# Placa_1.net
KiCad netlist of a schematic drawn in EAGLE
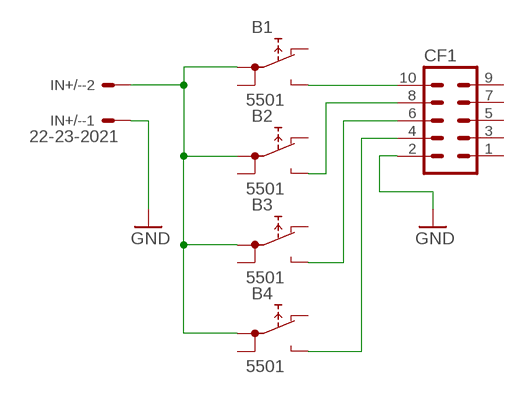
[diagram p0: schematic, sheet 1]

(export (version "E")
  (design (tool "Eeschema 10.0.6"))
  (components
    (comp (ref "B1")
      (value "5501")
      (footprint "eagle-import:5501")
      (libsource (lib "eagle-import") (part "55?01"))
    )
    (comp (ref "B2")
      (value "5501")
      (footprint "eagle-import:5501")
      (libsource (lib "eagle-import") (part "55?01"))
    )
    (comp (ref "B3")
      (value "5501")
      (footprint "eagle-import:5501")
      (libsource (lib "eagle-import") (part "55?01"))
    )
    (comp (ref "B4")
      (value "5501")
      (footprint "eagle-import:5501")
      (libsource (lib "eagle-import") (part "55?01"))
    )
    (comp (ref "CF1")
      (value "ML10")
      (footprint "eagle-import:ML10")
      (libsource (lib "eagle-import") (part "ML10"))
    )
    (comp (ref "IN+/-")
      (value "22-23-2021")
      (footprint "eagle-import:22-23-2021")
      (fields (field (name "MF") "MOLEX"))
      (libsource (lib "eagle-import") (part "22-23-2021"))
    )
  )
  (nets
    (net (code "1") (name "GND") (class "Default")
      (node (ref "CF1") (pin "2") (pinfunction "2_2") (pintype "passive"))
      (node (ref "IN+/-") (pin "1") (pinfunction "S_1") (pintype "passive"))
    )
    (net (code "2") (name "Net-(B1-PadNO)") (class "Default")
      (node (ref "B1") (pin "NO") (pinfunction "NO_NO") (pintype "passive"))
      (node (ref "CF1") (pin "10") (pinfunction "10_10") (pintype "passive"))
    )
    (net (code "3") (name "Net-(B2-PadNO)") (class "Default")
      (node (ref "B2") (pin "NO") (pinfunction "NO_NO") (pintype "passive"))
      (node (ref "CF1") (pin "8") (pinfunction "8_8") (pintype "passive"))
    )
    (net (code "4") (name "Net-(B3-PadNO)") (class "Default")
      (node (ref "B3") (pin "NO") (pinfunction "NO_NO") (pintype "passive"))
      (node (ref "CF1") (pin "6") (pinfunction "6_6") (pintype "passive"))
    )
    (net (code "5") (name "Net-(B4-PadNO)") (class "Default")
      (node (ref "B4") (pin "NO") (pinfunction "NO_NO") (pintype "passive"))
      (node (ref "CF1") (pin "4") (pinfunction "4_4") (pintype "passive"))
    )
    (net (code "6") (name "Net-(IN+/-B-S)") (class "Default")
      (node (ref "B1") (pin "1A") (pinfunction "1A_1A") (pintype "passive"))
      (node (ref "B2") (pin "1A") (pinfunction "1A_1A") (pintype "passive"))
      (node (ref "B3") (pin "1A") (pinfunction "1A_1A") (pintype "passive"))
      (node (ref "B4") (pin "1A") (pinfunction "1A_1A") (pintype "passive"))
      (node (ref "IN+/-") (pin "2") (pinfunction "S_2") (pintype "passive"))
    )
    (net (code "7") (name "unconnected-(B1-Pad1B)") (class "Default")
      (node (ref "B1") (pin "1B") (pinfunction "1B_1B") (pintype "passive"))
    )
    (net (code "8") (name "unconnected-(B1-PadNC)") (class "Default")
      (node (ref "B1") (pin "NC") (pinfunction "NC_NC") (pintype "passive"))
    )
    (net (code "9") (name "unconnected-(B2-Pad1B)") (class "Default")
      (node (ref "B2") (pin "1B") (pinfunction "1B_1B") (pintype "passive"))
    )
    (net (code "10") (name "unconnected-(B2-PadNC)") (class "Default")
      (node (ref "B2") (pin "NC") (pinfunction "NC_NC") (pintype "passive"))
    )
    (net (code "11") (name "unconnected-(B3-Pad1B)") (class "Default")
      (node (ref "B3") (pin "1B") (pinfunction "1B_1B") (pintype "passive"))
    )
    (net (code "12") (name "unconnected-(B3-PadNC)") (class "Default")
      (node (ref "B3") (pin "NC") (pinfunction "NC_NC") (pintype "passive"))
    )
    (net (code "13") (name "unconnected-(B4-Pad1B)") (class "Default")
      (node (ref "B4") (pin "1B") (pinfunction "1B_1B") (pintype "passive"))
    )
    (net (code "14") (name "unconnected-(B4-PadNC)") (class "Default")
      (node (ref "B4") (pin "NC") (pinfunction "NC_NC") (pintype "passive"))
    )
    (net (code "15") (name "unconnected-(CF1-Pad1)") (class "Default")
      (node (ref "CF1") (pin "1") (pinfunction "1_1") (pintype "passive"))
    )
    (net (code "16") (name "unconnected-(CF1-Pad3)") (class "Default")
      (node (ref "CF1") (pin "3") (pinfunction "3_3") (pintype "passive"))
    )
    (net (code "17") (name "unconnected-(CF1-Pad5)") (class "Default")
      (node (ref "CF1") (pin "5") (pinfunction "5_5") (pintype "passive"))
    )
    (net (code "18") (name "unconnected-(CF1-Pad7)") (class "Default")
      (node (ref "CF1") (pin "7") (pinfunction "7_7") (pintype "passive"))
    )
    (net (code "19") (name "unconnected-(CF1-Pad9)") (class "Default")
      (node (ref "CF1") (pin "9") (pinfunction "9_9") (pintype "passive"))
    )
  )
)
